# LB_BIT_i17_timeout-v03_rev1.net
KiCad netlist of a schematic drawn in EAGLE
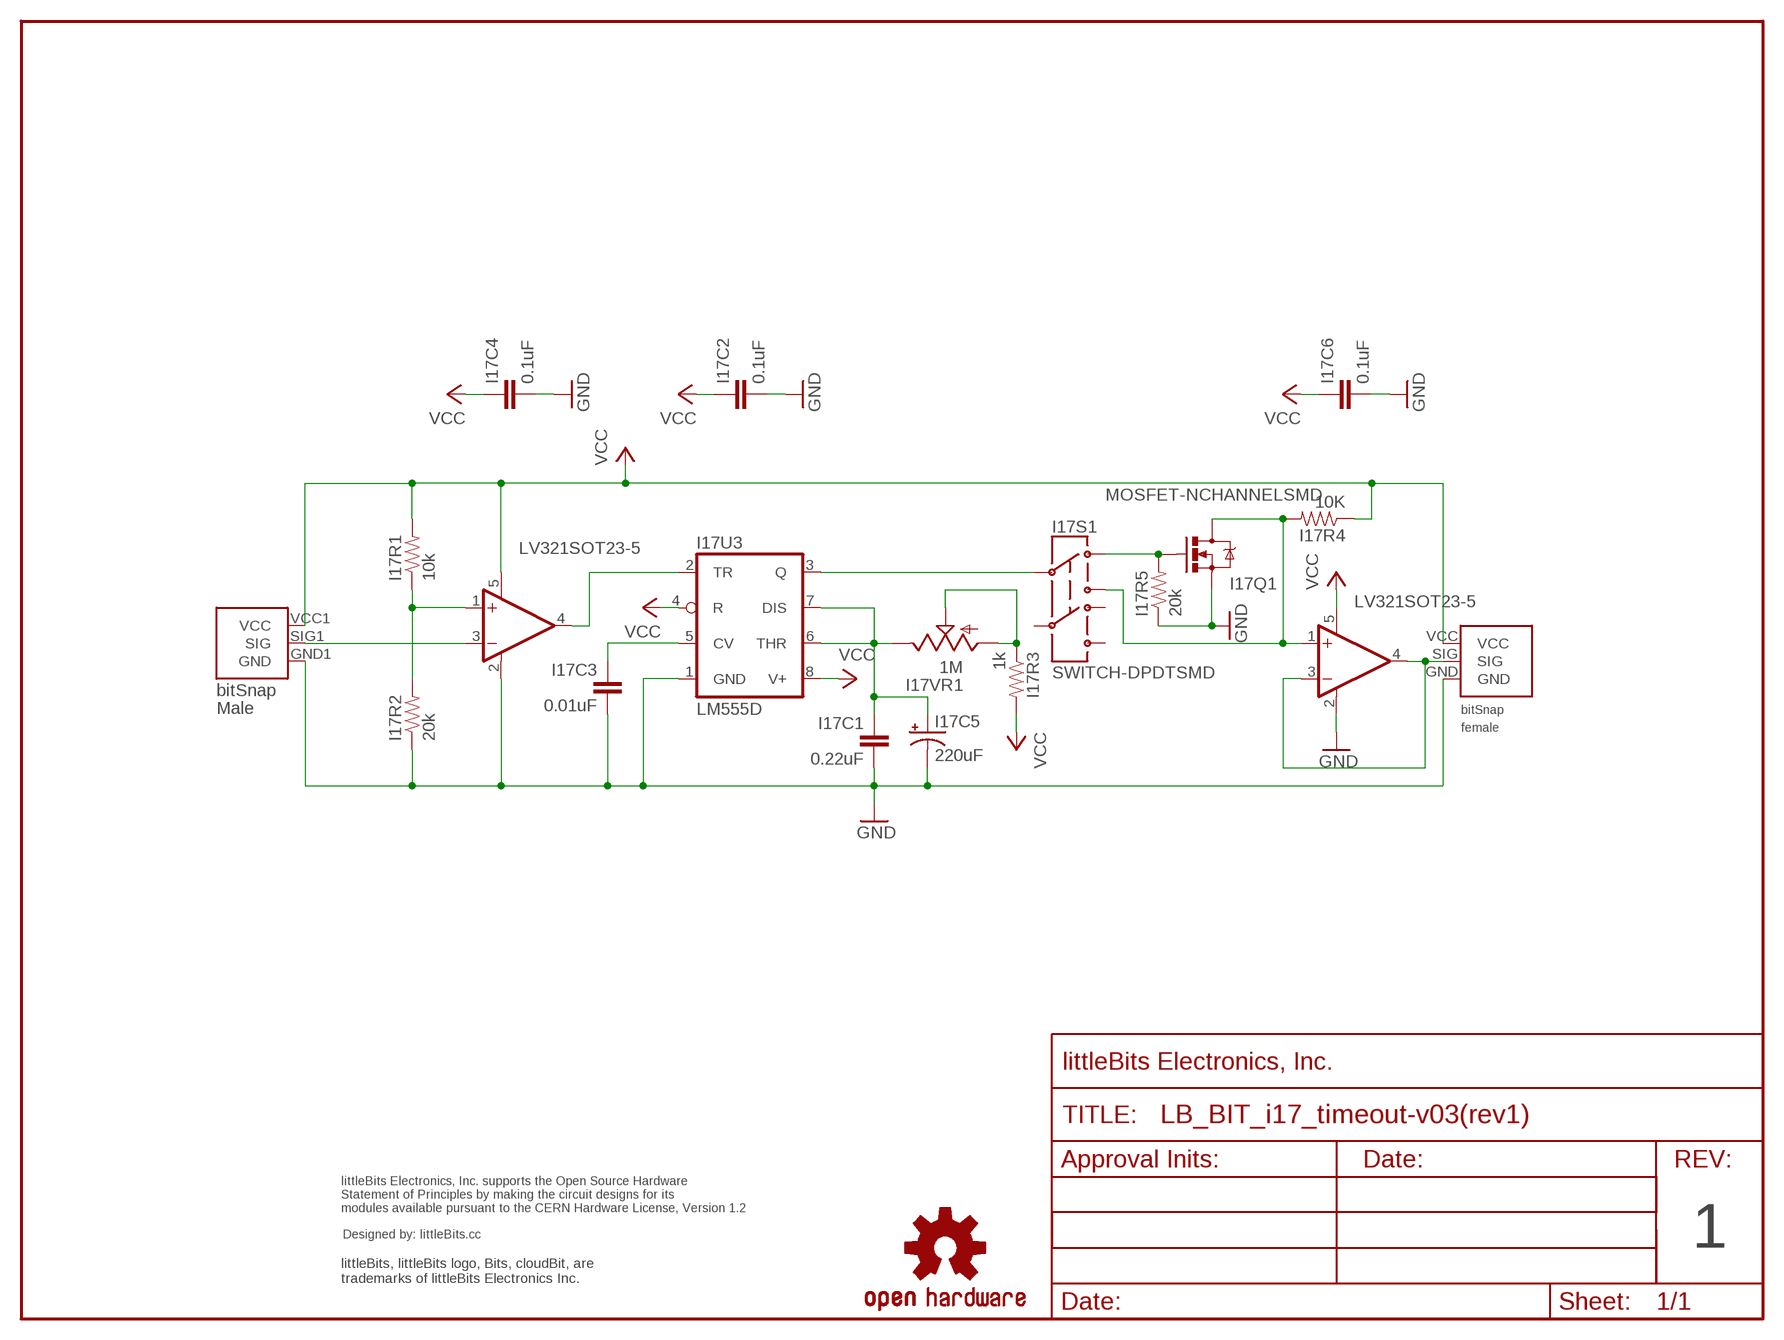
[diagram p0: schematic, sheet 1]

(export (version "E")
  (design (tool "Eeschema 10.0.6"))
  (components
    (comp (ref "I17BSF1")
      (value "BITSNAP_V03_FEMALE")
      (footprint "eagle-import:BITSNAP_V03_FEMALE")
      (libsource (lib "eagle-import") (part "BITSNAP_V03_FEMALE"))
    )
    (comp (ref "I17BSM1")
      (value "BITSNAP_V03_MALE")
      (footprint "eagle-import:BITSNAP_V03_MALE")
      (libsource (lib "eagle-import") (part "BITSNAP_V03_MALE"))
    )
    (comp (ref "I17C1")
      (value "0.22uF")
      (footprint "eagle-import:0603-CAP")
      (libsource (lib "eagle-import") (part "CAP0603-CAP"))
    )
    (comp (ref "I17C2")
      (value "0.1uF")
      (footprint "eagle-import:0603-CAP")
      (libsource (lib "eagle-import") (part "CAP0603-CAP"))
    )
    (comp (ref "I17C3")
      (value "0.01uF")
      (footprint "eagle-import:0603-CAP")
      (libsource (lib "eagle-import") (part "CAP0603-CAP"))
    )
    (comp (ref "I17C4")
      (value "0.1uF")
      (footprint "eagle-import:0603-CAP")
      (libsource (lib "eagle-import") (part "CAP0603-CAP"))
    )
    (comp (ref "I17C5")
      (value "220uF")
      (footprint "eagle-import:PANASONIC_D")
      (libsource (lib "eagle-import") (part "CAP_POLD"))
    )
    (comp (ref "I17C6")
      (value "0.1uF")
      (footprint "eagle-import:0603-CAP")
      (libsource (lib "eagle-import") (part "CAP0603-CAP"))
    )
    (comp (ref "I17Q1")
      (value "MOSFET-NCHANNELSMD")
      (footprint "eagle-import:SOT23-3")
      (libsource (lib "eagle-import") (part "MOSFET-NCHANNELSMD"))
    )
    (comp (ref "I17R1")
      (value "10k")
      (footprint "eagle-import:0603-RES")
      (libsource (lib "eagle-import") (part "RESISTOR0603-RES"))
    )
    (comp (ref "I17R2")
      (value "20k")
      (footprint "eagle-import:0603-RES")
      (libsource (lib "eagle-import") (part "RESISTOR0603-RES"))
    )
    (comp (ref "I17R3")
      (value "1k")
      (footprint "eagle-import:0603-RES")
      (libsource (lib "eagle-import") (part "RESISTOR0603-RES"))
    )
    (comp (ref "I17R4")
      (value "10K")
      (footprint "eagle-import:0603-RES")
      (libsource (lib "eagle-import") (part "RESISTOR0603-RES"))
    )
    (comp (ref "I17R5")
      (value "20k")
      (footprint "eagle-import:0603-RES")
      (libsource (lib "eagle-import") (part "RESISTOR0603-RES"))
    )
    (comp (ref "I17S1")
      (value "SWITCH-DPDTSMD")
      (footprint "eagle-import:AYZ0202")
      (libsource (lib "eagle-import") (part "SWITCH-DPDTSMD"))
    )
    (comp (ref "I17U1")
      (value "LV321SOT23-5")
      (footprint "eagle-import:SOT23-5")
      (libsource (lib "eagle-import") (part "LV321SOT23-5"))
    )
    (comp (ref "I17U2")
      (value "LV321SOT23-5")
      (footprint "eagle-import:SOT23-5")
      (libsource (lib "eagle-import") (part "LV321SOT23-5"))
    )
    (comp (ref "I17U3")
      (value "LM555D")
      (footprint "eagle-import:SO08")
      (libsource (lib "eagle-import") (part "555DLM"))
    )
    (comp (ref "I17VR1")
      (value "1M")
      (footprint "eagle-import:POT-TRIM-SMD-BOURNS-3303")
      (libsource (lib "eagle-import") (part "POT-TRIM-SMD-BOURNS-3303"))
    )
    (comp (ref "U$1")
      (value "OSHWCREDIT")
      (footprint "eagle-import:OSHWCREDIT")
      (libsource (lib "eagle-import") (part "OSHWCREDIT"))
    )
    (comp (ref "U$2")
      (value "FRAME-LETTER-OHWOHW")
      (footprint "eagle-import:FABDWG01-OHW")
      (libsource (lib "eagle-import") (part "FRAME-LETTER-OHWOHW"))
    )
    (comp (ref "U$4")
      (value "OSHW-LOGOL")
      (footprint "eagle-import:OSHW-LOGO-L")
      (libsource (lib "eagle-import") (part "OSHW-LOGOL"))
    )
  )
  (nets
    (net (code "1") (name "GND") (class "Default")
      (node (ref "I17BSF1") (pin "GND") (pinfunction "GND_GND") (pintype "bidirectional"))
      (node (ref "I17BSM1") (pin "GND1") (pinfunction "GND_GND1") (pintype "bidirectional"))
      (node (ref "I17C1") (pin "2") (pinfunction "2_2") (pintype "passive"))
      (node (ref "I17C2") (pin "2") (pinfunction "2_2") (pintype "passive"))
      (node (ref "I17C3") (pin "2") (pinfunction "2_2") (pintype "passive"))
      (node (ref "I17C4") (pin "2") (pinfunction "2_2") (pintype "passive"))
      (node (ref "I17C5") (pin "-") (pinfunction "-_-") (pintype "passive"))
      (node (ref "I17C6") (pin "2") (pinfunction "2_2") (pintype "passive"))
      (node (ref "I17Q1") (pin "2") (pinfunction "S_2") (pintype "passive"))
      (node (ref "I17R2") (pin "1") (pinfunction "1_1") (pintype "passive"))
      (node (ref "I17R5") (pin "1") (pinfunction "1_1") (pintype "passive"))
      (node (ref "I17U1") (pin "2") (pinfunction "V-_2") (pintype "power_in"))
      (node (ref "I17U2") (pin "2") (pinfunction "V-_2") (pintype "power_in"))
      (node (ref "I17U3") (pin "1") (pinfunction "GND_1") (pintype "power_in"))
    )
    (net (code "2") (name "Net-(I17BSM1-SIG)") (class "Default")
      (node (ref "I17BSM1") (pin "SIG1") (pinfunction "SIG_SIG1") (pintype "bidirectional"))
      (node (ref "I17U1") (pin "3") (pinfunction "-IN_3") (pintype "input"))
    )
    (net (code "3") (name "Net-(I17Q1-D)") (class "Default")
      (node (ref "I17Q1") (pin "3") (pinfunction "D_3") (pintype "passive"))
      (node (ref "I17R4") (pin "2") (pinfunction "2_2") (pintype "passive"))
      (node (ref "I17S1") (pin "3") (pinfunction "3_3") (pintype "bidirectional"))
      (node (ref "I17U2") (pin "1") (pinfunction "+IN_1") (pintype "input"))
    )
    (net (code "4") (name "Net-(I17Q1-G)") (class "Default")
      (node (ref "I17Q1") (pin "1") (pinfunction "G_1") (pintype "passive"))
      (node (ref "I17R5") (pin "2") (pinfunction "2_2") (pintype "passive"))
      (node (ref "I17S1") (pin "1") (pinfunction "1_1") (pintype "bidirectional"))
    )
    (net (code "5") (name "Net-(I17U1-+IN)") (class "Default")
      (node (ref "I17R1") (pin "1") (pinfunction "1_1") (pintype "passive"))
      (node (ref "I17R2") (pin "2") (pinfunction "2_2") (pintype "passive"))
      (node (ref "I17U1") (pin "1") (pinfunction "+IN_1") (pintype "input"))
    )
    (net (code "6") (name "Net-(I17U1-OUT)") (class "Default")
      (node (ref "I17U1") (pin "4") (pinfunction "OUT_4") (pintype "output"))
      (node (ref "I17U3") (pin "2") (pinfunction "TR_2") (pintype "input"))
    )
    (net (code "7") (name "Net-(I17U2--IN)") (class "Default")
      (node (ref "I17BSF1") (pin "SIG") (pinfunction "SIG_SIG") (pintype "bidirectional"))
      (node (ref "I17U2") (pin "3") (pinfunction "-IN_3") (pintype "input"))
      (node (ref "I17U2") (pin "4") (pinfunction "OUT_4") (pintype "output"))
    )
    (net (code "8") (name "Net-(I17U3-CV)") (class "Default")
      (node (ref "I17C3") (pin "1") (pinfunction "1_1") (pintype "passive"))
      (node (ref "I17U3") (pin "5") (pinfunction "CV_5") (pintype "input"))
    )
    (net (code "9") (name "Net-(I17U3-DIS)") (class "Default")
      (node (ref "I17C1") (pin "1") (pinfunction "1_1") (pintype "passive"))
      (node (ref "I17C5") (pin "+") (pinfunction "+_+") (pintype "passive"))
      (node (ref "I17U3") (pin "6") (pinfunction "THR_6") (pintype "input"))
      (node (ref "I17U3") (pin "7") (pinfunction "DIS_7") (pintype "input"))
      (node (ref "I17VR1") (pin "3") (pinfunction "E_3") (pintype "passive"))
    )
    (net (code "10") (name "Net-(I17U3-Q)") (class "Default")
      (node (ref "I17S1") (pin "2") (pinfunction "2_2") (pintype "bidirectional"))
      (node (ref "I17U3") (pin "3") (pinfunction "Q_3") (pintype "output"))
    )
    (net (code "11") (name "Net-(I17VR1-A)") (class "Default")
      (node (ref "I17R3") (pin "1") (pinfunction "1_1") (pintype "passive"))
      (node (ref "I17VR1") (pin "1") (pinfunction "A_1") (pintype "passive"))
      (node (ref "I17VR1") (pin "2") (pinfunction "S_2") (pintype "passive"))
    )
    (net (code "12") (name "VCC") (class "Default")
      (node (ref "I17BSF1") (pin "VCC") (pinfunction "VCC_VCC") (pintype "bidirectional"))
      (node (ref "I17BSM1") (pin "VCC1") (pinfunction "VCC_VCC1") (pintype "bidirectional"))
      (node (ref "I17C2") (pin "1") (pinfunction "1_1") (pintype "passive"))
      (node (ref "I17C4") (pin "1") (pinfunction "1_1") (pintype "passive"))
      (node (ref "I17C6") (pin "1") (pinfunction "1_1") (pintype "passive"))
      (node (ref "I17R1") (pin "2") (pinfunction "2_2") (pintype "passive"))
      (node (ref "I17R3") (pin "2") (pinfunction "2_2") (pintype "passive"))
      (node (ref "I17R4") (pin "1") (pinfunction "1_1") (pintype "passive"))
      (node (ref "I17U1") (pin "5") (pinfunction "V+_5") (pintype "power_in"))
      (node (ref "I17U2") (pin "5") (pinfunction "V+_5") (pintype "power_in"))
      (node (ref "I17U3") (pin "4") (pinfunction "R_4") (pintype "input"))
      (node (ref "I17U3") (pin "8") (pinfunction "V+_8") (pintype "power_in"))
    )
    (net (code "13") (name "unconnected-(I17S1-Pad4)") (class "Default")
      (node (ref "I17S1") (pin "4") (pinfunction "4_4") (pintype "bidirectional"))
    )
    (net (code "14") (name "unconnected-(I17S1-Pad5)") (class "Default")
      (node (ref "I17S1") (pin "5") (pinfunction "5_5") (pintype "bidirectional"))
    )
    (net (code "15") (name "unconnected-(I17S1-Pad6)") (class "Default")
      (node (ref "I17S1") (pin "6") (pinfunction "6_6") (pintype "bidirectional"))
    )
  )
)
